# test_saving.net
KiCad netlist of a schematic drawn in EAGLE
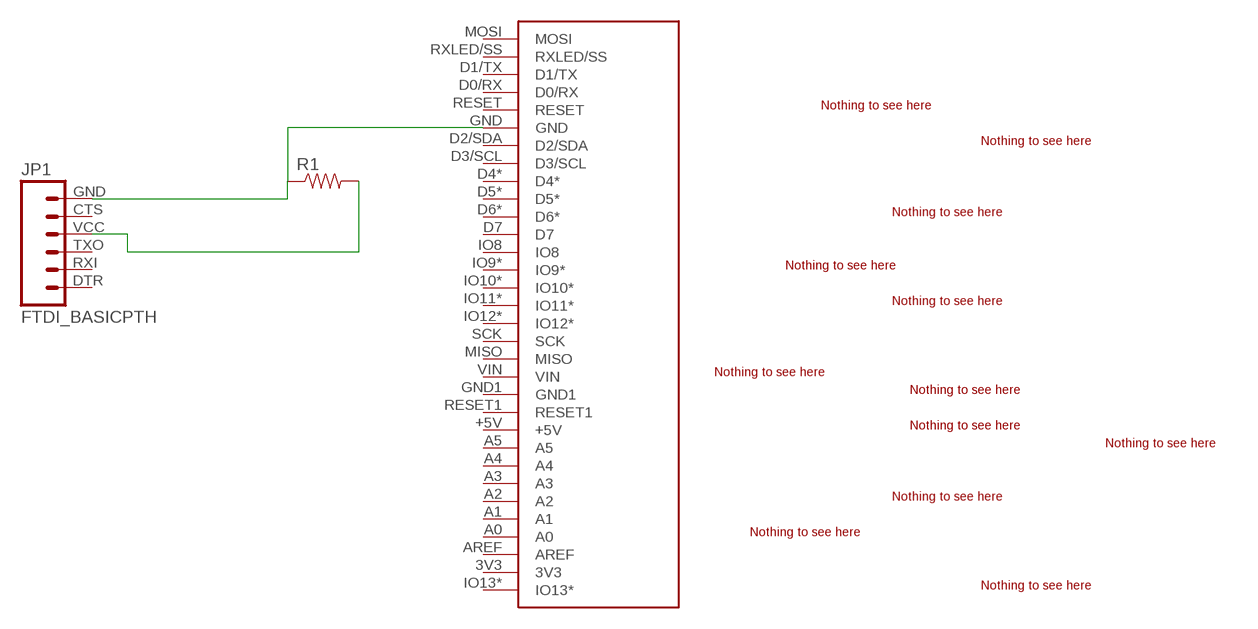
[diagram p0: schematic, sheet 1]

(export (version "E")
  (design (tool "Eeschema 10.0.6"))
  (components
    (comp (ref "ARDUINO")
      (value "ARDUINO_MICRO_REV03J-BOB")
      (footprint "eagle-import:ARDUINO_MICRO_REV03J")
      (libsource (lib "eagle-import") (part "ARDUINO_MICRO_REV03J-BOB"))
    )
    (comp (ref "JP1")
      (value "FTDI_BASICPTH")
      (footprint "eagle-import:FTDI_BASIC")
      (libsource (lib "eagle-import") (part "FTDI_BASICPTH"))
    )
    (comp (ref "R1")
      (value "RESISTOR0805-RES")
      (footprint "eagle-import:0805")
      (libsource (lib "eagle-import") (part "RESISTOR0805-RES"))
    )
    (comp (ref "TEST-ARC1")
      (value "TEST-ARC")
      (footprint "eagle-import:TEST-ARC")
      (libsource (lib "eagle-import") (part "TEST-ARC"))
    )
    (comp (ref "TEST-ARC3")
      (value "TEST-ARC3")
      (footprint "eagle-import:TEST-ARC3")
      (libsource (lib "eagle-import") (part "TEST-ARC3"))
    )
    (comp (ref "TEST-CIRCLE")
      (value "TEST-CIRCLE")
      (footprint "eagle-import:TEST-CIRCLE")
      (libsource (lib "eagle-import") (part "TEST-CIRCLE"))
    )
    (comp (ref "TEST-HOLE")
      (value "TEST-HOLE")
      (footprint "eagle-import:TEST-HOLE")
      (libsource (lib "eagle-import") (part "TEST-HOLE"))
    )
    (comp (ref "TEST-PAD-OCT")
      (value "TEST-PAD-OCT")
      (footprint "eagle-import:TEST-PAD-OCT")
      (libsource (lib "eagle-import") (part "TEST-PAD-OCT"))
    )
    (comp (ref "TEST-PAD-OCT2")
      (value "TEST-PAD-OCT2")
      (footprint "eagle-import:TEST-PAD-OCT2")
      (libsource (lib "eagle-import") (part "TEST-PAD-OCT2"))
    )
    (comp (ref "TEST-PAD-ROT")
      (value "TEST-PAD-ROT")
      (footprint "eagle-import:TEST-PAD-ROT")
      (libsource (lib "eagle-import") (part "TEST-PAD-ROT"))
    )
    (comp (ref "TEST-PAD-ROUND")
      (value "TEST-PAD-ROUND")
      (footprint "eagle-import:TEST-PAD-ROUND")
      (libsource (lib "eagle-import") (part "TEST-PAD-ROUND"))
    )
    (comp (ref "TEST-PAD-SQUARE")
      (value "TEST-PAD3")
      (footprint "eagle-import:TEST-PAD3")
      (libsource (lib "eagle-import") (part "TEST-PAD3"))
    )
    (comp (ref "TEST-PAD-SQUARE-ROT")
      (value "TEST-PAD-SQUARE-ROT")
      (footprint "eagle-import:TEST-PAD-SQUARE-ROT")
      (libsource (lib "eagle-import") (part "TEST-PAD-SQUARE-ROT"))
    )
    (comp (ref "TEST-PAD1")
      (value "TEST-PAD1")
      (footprint "eagle-import:TEST-PAD1")
      (libsource (lib "eagle-import") (part "TEST-PAD1"))
    )
    (comp (ref "TEST-PAD2")
      (value "TEST-PAD2")
      (footprint "eagle-import:TEST-PAD2")
      (libsource (lib "eagle-import") (part "TEST-PAD2"))
    )
  )
  (nets
    (net (code "1") (name "Net-(JP1-4)") (class "Default")
      (node (ref "JP1") (pin "VCC") (pinfunction "4_VCC") (pintype "passive"))
      (node (ref "R1") (pin "2") (pinfunction "2_2") (pintype "passive"))
    )
    (net (code "2") (name "Net-(JP1-6)") (class "Default")
      (node (ref "ARDUINO") (pin "GND") (pinfunction "GND_GND") (pintype "bidirectional"))
      (node (ref "JP1") (pin "GND") (pinfunction "6_GND") (pintype "passive"))
      (node (ref "R1") (pin "1") (pinfunction "1_1") (pintype "passive"))
    )
    (net (code "3") (name "unconnected-(ARDUINO-Pad+5V)") (class "Default")
      (node (ref "ARDUINO") (pin "+5V") (pinfunction "+5V_+5V") (pintype "bidirectional"))
    )
    (net (code "4") (name "unconnected-(ARDUINO-Pad3V3)") (class "Default")
      (node (ref "ARDUINO") (pin "3V3") (pinfunction "3V3_3V3") (pintype "bidirectional"))
    )
    (net (code "5") (name "unconnected-(ARDUINO-PadA0)") (class "Default")
      (node (ref "ARDUINO") (pin "A0") (pinfunction "A0_A0") (pintype "bidirectional"))
    )
    (net (code "6") (name "unconnected-(ARDUINO-PadA1)") (class "Default")
      (node (ref "ARDUINO") (pin "A1") (pinfunction "A1_A1") (pintype "bidirectional"))
    )
    (net (code "7") (name "unconnected-(ARDUINO-PadA2)") (class "Default")
      (node (ref "ARDUINO") (pin "A2") (pinfunction "A2_A2") (pintype "bidirectional"))
    )
    (net (code "8") (name "unconnected-(ARDUINO-PadA3)") (class "Default")
      (node (ref "ARDUINO") (pin "A3") (pinfunction "A3_A3") (pintype "bidirectional"))
    )
    (net (code "9") (name "unconnected-(ARDUINO-PadA4)") (class "Default")
      (node (ref "ARDUINO") (pin "A4") (pinfunction "A4_A4") (pintype "bidirectional"))
    )
    (net (code "10") (name "unconnected-(ARDUINO-PadA5)") (class "Default")
      (node (ref "ARDUINO") (pin "A5") (pinfunction "A5_A5") (pintype "bidirectional"))
    )
    (net (code "11") (name "unconnected-(ARDUINO-PadAREF)") (class "Default")
      (node (ref "ARDUINO") (pin "AREF") (pinfunction "AREF_AREF") (pintype "bidirectional"))
    )
    (net (code "12") (name "unconnected-(ARDUINO-PadD0{slash}RX)") (class "Default")
      (node (ref "ARDUINO") (pin "D0/RX") (pinfunction "D0/RX_D0/RX") (pintype "bidirectional"))
    )
    (net (code "13") (name "unconnected-(ARDUINO-PadD1{slash}TX)") (class "Default")
      (node (ref "ARDUINO") (pin "D1/TX") (pinfunction "D1/TX_D1/TX") (pintype "bidirectional"))
    )
    (net (code "14") (name "unconnected-(ARDUINO-PadD2{slash}SDA)") (class "Default")
      (node (ref "ARDUINO") (pin "D2/SDA") (pinfunction "D2/SDA_D2/SDA") (pintype "bidirectional"))
    )
    (net (code "15") (name "unconnected-(ARDUINO-PadD3{slash}SCL)") (class "Default")
      (node (ref "ARDUINO") (pin "D3/SCL") (pinfunction "D3/SCL_D3/SCL") (pintype "bidirectional"))
    )
    (net (code "16") (name "unconnected-(ARDUINO-PadD4*)") (class "Default")
      (node (ref "ARDUINO") (pin "D4*") (pinfunction "D4*_D4*") (pintype "bidirectional"))
    )
    (net (code "17") (name "unconnected-(ARDUINO-PadD5*)") (class "Default")
      (node (ref "ARDUINO") (pin "D5*") (pinfunction "D5*_D5*") (pintype "bidirectional"))
    )
    (net (code "18") (name "unconnected-(ARDUINO-PadD6*)") (class "Default")
      (node (ref "ARDUINO") (pin "D6*") (pinfunction "D6*_D6*") (pintype "bidirectional"))
    )
    (net (code "19") (name "unconnected-(ARDUINO-PadD7)") (class "Default")
      (node (ref "ARDUINO") (pin "D7") (pinfunction "D7_D7") (pintype "bidirectional"))
    )
    (net (code "20") (name "unconnected-(ARDUINO-PadGND1)") (class "Default")
      (node (ref "ARDUINO") (pin "GND1") (pinfunction "GND1_GND1") (pintype "bidirectional"))
    )
    (net (code "21") (name "unconnected-(ARDUINO-PadIO8)") (class "Default")
      (node (ref "ARDUINO") (pin "IO8") (pinfunction "IO8_IO8") (pintype "bidirectional"))
    )
    (net (code "22") (name "unconnected-(ARDUINO-PadIO9*)") (class "Default")
      (node (ref "ARDUINO") (pin "IO9*") (pinfunction "IO9*_IO9*") (pintype "bidirectional"))
    )
    (net (code "23") (name "unconnected-(ARDUINO-PadIO10*)") (class "Default")
      (node (ref "ARDUINO") (pin "IO10*") (pinfunction "IO10*_IO10*") (pintype "bidirectional"))
    )
    (net (code "24") (name "unconnected-(ARDUINO-PadIO11*)") (class "Default")
      (node (ref "ARDUINO") (pin "IO11*") (pinfunction "IO11*_IO11*") (pintype "bidirectional"))
    )
    (net (code "25") (name "unconnected-(ARDUINO-PadIO12*)") (class "Default")
      (node (ref "ARDUINO") (pin "IO12*") (pinfunction "IO12*_IO12*") (pintype "bidirectional"))
    )
    (net (code "26") (name "unconnected-(ARDUINO-PadIO13*)") (class "Default")
      (node (ref "ARDUINO") (pin "IO13*") (pinfunction "IO13*_IO13*") (pintype "bidirectional"))
    )
    (net (code "27") (name "unconnected-(ARDUINO-PadMISO)") (class "Default")
      (node (ref "ARDUINO") (pin "MISO") (pinfunction "MISO_MISO") (pintype "bidirectional"))
    )
    (net (code "28") (name "unconnected-(ARDUINO-PadMOSI)") (class "Default")
      (node (ref "ARDUINO") (pin "MOSI") (pinfunction "MOSI_MOSI") (pintype "bidirectional"))
    )
    (net (code "29") (name "unconnected-(ARDUINO-PadRESET)") (class "Default")
      (node (ref "ARDUINO") (pin "RESET") (pinfunction "RESET_RESET") (pintype "bidirectional"))
    )
    (net (code "30") (name "unconnected-(ARDUINO-PadRESET1)") (class "Default")
      (node (ref "ARDUINO") (pin "RESET1") (pinfunction "RESET1_RESET1") (pintype "bidirectional"))
    )
    (net (code "31") (name "unconnected-(ARDUINO-PadRXLED{slash}SS)") (class "Default")
      (node (ref "ARDUINO") (pin "RXLED/SS") (pinfunction "RXLED/SS_RXLED/SS") (pintype "bidirectional"))
    )
    (net (code "32") (name "unconnected-(ARDUINO-PadSCK)") (class "Default")
      (node (ref "ARDUINO") (pin "SCK") (pinfunction "SCK_SCK") (pintype "bidirectional"))
    )
    (net (code "33") (name "unconnected-(ARDUINO-PadVIN)") (class "Default")
      (node (ref "ARDUINO") (pin "VIN") (pinfunction "VIN_VIN") (pintype "bidirectional"))
    )
    (net (code "34") (name "unconnected-(JP1-1-PadDTR)") (class "Default")
      (node (ref "JP1") (pin "DTR") (pinfunction "1_DTR") (pintype "passive"))
    )
    (net (code "35") (name "unconnected-(JP1-2-PadRXI)") (class "Default")
      (node (ref "JP1") (pin "RXI") (pinfunction "2_RXI") (pintype "passive"))
    )
    (net (code "36") (name "unconnected-(JP1-3-PadTXO)") (class "Default")
      (node (ref "JP1") (pin "TXO") (pinfunction "3_TXO") (pintype "passive"))
    )
    (net (code "37") (name "unconnected-(JP1-5-PadCTS)") (class "Default")
      (node (ref "JP1") (pin "CTS") (pinfunction "5_CTS") (pintype "passive"))
    )
  )
)
